# Woolllf_Open_Weeve.net
KiCad netlist of a schematic drawn in EAGLE
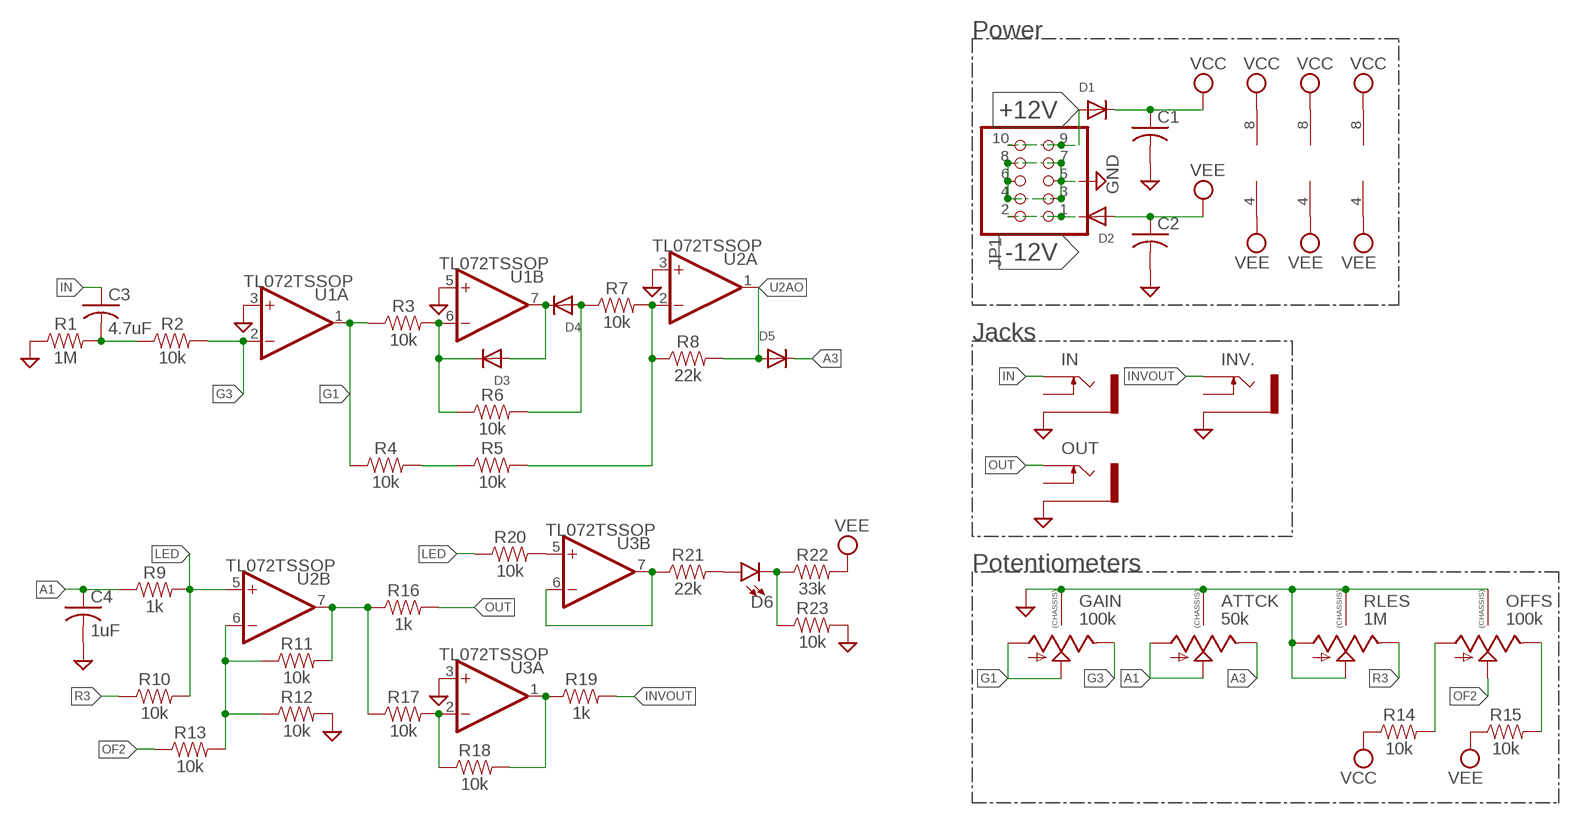
[diagram p0: schematic, sheet 1]

(export (version "E")
  (design (tool "Eeschema 10.0.6"))
  (components
    (comp (ref "ATTCK")
      (value "50k")
      (footprint "eagle-import:9MM_SNAP-IN_POT")
      (libsource (lib "eagle-import") (part "9MM_SNAP-IN_POT_CHASSIS"))
    )
    (comp (ref "C1")
      (value "C-USC1206")
      (footprint "eagle-import:C1206")
      (libsource (lib "eagle-import") (part "C-USC1206"))
    )
    (comp (ref "C2")
      (value "C-USC1206")
      (footprint "eagle-import:C1206")
      (libsource (lib "eagle-import") (part "C-USC1206"))
    )
    (comp (ref "C3")
      (value "4.7uF")
      (footprint "eagle-import:C0603")
      (libsource (lib "eagle-import") (part "C-USC0603"))
    )
    (comp (ref "C4")
      (value "1uF")
      (footprint "eagle-import:C0603")
      (libsource (lib "eagle-import") (part "C-USC0603"))
    )
    (comp (ref "D1")
      (value "DIODESOD-123")
      (footprint "eagle-import:SOD-123")
      (libsource (lib "eagle-import") (part "DIODESOD-123"))
    )
    (comp (ref "D2")
      (value "DIODESOD-123")
      (footprint "eagle-import:SOD-123")
      (libsource (lib "eagle-import") (part "DIODESOD-123"))
    )
    (comp (ref "D3")
      (value "DIODESOD-123")
      (footprint "eagle-import:SOD-123")
      (libsource (lib "eagle-import") (part "DIODESOD-123"))
    )
    (comp (ref "D4")
      (value "DIODESOD-123")
      (footprint "eagle-import:SOD-123")
      (libsource (lib "eagle-import") (part "DIODESOD-123"))
    )
    (comp (ref "D5")
      (value "DIODESOD-123")
      (footprint "eagle-import:SOD-123")
      (libsource (lib "eagle-import") (part "DIODESOD-123"))
    )
    (comp (ref "D6")
      (value "LED3MM")
      (footprint "eagle-import:LED_3MM")
      (libsource (lib "eagle-import") (part "LED3MM"))
    )
    (comp (ref "GAIN")
      (value "100k")
      (footprint "eagle-import:9MM_SNAP-IN_POT")
      (libsource (lib "eagle-import") (part "9MM_SNAP-IN_POT_CHASSIS"))
    )
    (comp (ref "IN")
      (value "THONKICONNOLD")
      (footprint "eagle-import:THONKICONN")
      (libsource (lib "eagle-import") (part "THONKICONNOLD"))
    )
    (comp (ref "INV.")
      (value "THONKICONNOLD")
      (footprint "eagle-import:THONKICONN")
      (libsource (lib "eagle-import") (part "THONKICONNOLD"))
    )
    (comp (ref "JP1")
      (value "PINHD-2X5")
      (footprint "eagle-import:2X05")
      (libsource (lib "eagle-import") (part "PINHD-2X5"))
    )
    (comp (ref "OFFS")
      (value "100k")
      (footprint "eagle-import:9MM_SNAP-IN_POT")
      (libsource (lib "eagle-import") (part "9MM_SNAP-IN_POT_CHASSIS"))
    )
    (comp (ref "OUT")
      (value "THONKICONNOLD")
      (footprint "eagle-import:THONKICONN")
      (libsource (lib "eagle-import") (part "THONKICONNOLD"))
    )
    (comp (ref "R1")
      (value "1M")
      (footprint "eagle-import:0603")
      (libsource (lib "eagle-import") (part "RESISTOR0603"))
    )
    (comp (ref "R2")
      (value "10k")
      (footprint "eagle-import:0603")
      (libsource (lib "eagle-import") (part "RESISTOR0603"))
    )
    (comp (ref "R3")
      (value "10k")
      (footprint "eagle-import:0603")
      (libsource (lib "eagle-import") (part "RESISTOR0603"))
    )
    (comp (ref "R4")
      (value "10k")
      (footprint "eagle-import:0603")
      (libsource (lib "eagle-import") (part "RESISTOR0603"))
    )
    (comp (ref "R5")
      (value "10k")
      (footprint "eagle-import:0603")
      (libsource (lib "eagle-import") (part "RESISTOR0603"))
    )
    (comp (ref "R6")
      (value "10k")
      (footprint "eagle-import:0603")
      (libsource (lib "eagle-import") (part "RESISTOR0603"))
    )
    (comp (ref "R7")
      (value "10k")
      (footprint "eagle-import:0603")
      (libsource (lib "eagle-import") (part "RESISTOR0603"))
    )
    (comp (ref "R8")
      (value "22k")
      (footprint "eagle-import:0603")
      (libsource (lib "eagle-import") (part "RESISTOR0603"))
    )
    (comp (ref "R9")
      (value "1k")
      (footprint "eagle-import:0603")
      (libsource (lib "eagle-import") (part "RESISTOR0603"))
    )
    (comp (ref "R10")
      (value "10k")
      (footprint "eagle-import:0603")
      (libsource (lib "eagle-import") (part "RESISTOR0603"))
    )
    (comp (ref "R11")
      (value "10k")
      (footprint "eagle-import:0603")
      (libsource (lib "eagle-import") (part "RESISTOR0603"))
    )
    (comp (ref "R12")
      (value "10k")
      (footprint "eagle-import:0603")
      (libsource (lib "eagle-import") (part "RESISTOR0603"))
    )
    (comp (ref "R13")
      (value "10k")
      (footprint "eagle-import:0603")
      (libsource (lib "eagle-import") (part "RESISTOR0603"))
    )
    (comp (ref "R14")
      (value "10k")
      (footprint "eagle-import:0603")
      (libsource (lib "eagle-import") (part "RESISTOR0603"))
    )
    (comp (ref "R15")
      (value "10k")
      (footprint "eagle-import:0603")
      (libsource (lib "eagle-import") (part "RESISTOR0603"))
    )
    (comp (ref "R16")
      (value "1k")
      (footprint "eagle-import:0603")
      (libsource (lib "eagle-import") (part "RESISTOR0603"))
    )
    (comp (ref "R17")
      (value "10k")
      (footprint "eagle-import:0603")
      (libsource (lib "eagle-import") (part "RESISTOR0603"))
    )
    (comp (ref "R18")
      (value "10k")
      (footprint "eagle-import:0603")
      (libsource (lib "eagle-import") (part "RESISTOR0603"))
    )
    (comp (ref "R19")
      (value "1k")
      (footprint "eagle-import:0603")
      (libsource (lib "eagle-import") (part "RESISTOR0603"))
    )
    (comp (ref "R20")
      (value "10k")
      (footprint "eagle-import:0603")
      (libsource (lib "eagle-import") (part "RESISTOR0603"))
    )
    (comp (ref "R21")
      (value "22k")
      (footprint "eagle-import:0603")
      (libsource (lib "eagle-import") (part "RESISTOR0603"))
    )
    (comp (ref "R22")
      (value "33k")
      (footprint "eagle-import:0603")
      (libsource (lib "eagle-import") (part "RESISTOR0603"))
    )
    (comp (ref "R23")
      (value "10k")
      (footprint "eagle-import:0603")
      (libsource (lib "eagle-import") (part "RESISTOR0603"))
    )
    (comp (ref "RLES")
      (value "1M")
      (footprint "eagle-import:9MM_SNAP-IN_POT")
      (libsource (lib "eagle-import") (part "9MM_SNAP-IN_POT_CHASSIS"))
    )
    (comp (ref "U1")
      (value "TL072TSSOP")
      (footprint "eagle-import:TSSOP-8")
      (libsource (lib "eagle-import") (part "TL072TSSOP"))
    )
    (comp (ref "U2")
      (value "TL072TSSOP")
      (footprint "eagle-import:TSSOP-8")
      (libsource (lib "eagle-import") (part "TL072TSSOP"))
    )
    (comp (ref "U3")
      (value "TL072TSSOP")
      (footprint "eagle-import:TSSOP-8")
      (libsource (lib "eagle-import") (part "TL072TSSOP"))
    )
  )
  (nets
    (net (code "1") (name "+12V") (class "Default")
      (node (ref "D1") (pin "A") (pinfunction "A_A") (pintype "passive"))
      (node (ref "JP1") (pin "10") (pinfunction "10_10") (pintype "passive"))
      (node (ref "JP1") (pin "9") (pinfunction "9_9") (pintype "passive"))
    )
    (net (code "2") (name "-12V") (class "Default")
      (node (ref "D2") (pin "C") (pinfunction "C_C") (pintype "passive"))
      (node (ref "JP1") (pin "1") (pinfunction "1_1") (pintype "passive"))
      (node (ref "JP1") (pin "2") (pinfunction "2_2") (pintype "passive"))
    )
    (net (code "3") (name "A1") (class "Default")
      (node (ref "ATTCK") (pin "1") (pinfunction "A_1") (pintype "passive"))
      (node (ref "ATTCK") (pin "2") (pinfunction "S_2") (pintype "passive"))
      (node (ref "C4") (pin "1") (pinfunction "1_1") (pintype "passive"))
      (node (ref "R9") (pin "1") (pinfunction "1_1") (pintype "passive"))
    )
    (net (code "4") (name "A3") (class "Default")
      (node (ref "ATTCK") (pin "3") (pinfunction "E_3") (pintype "passive"))
      (node (ref "D5") (pin "C") (pinfunction "C_C") (pintype "passive"))
    )
    (net (code "5") (name "G1") (class "Default")
      (node (ref "GAIN") (pin "1") (pinfunction "A_1") (pintype "passive"))
      (node (ref "GAIN") (pin "2") (pinfunction "S_2") (pintype "passive"))
      (node (ref "R3") (pin "1") (pinfunction "1_1") (pintype "passive"))
      (node (ref "R4") (pin "1") (pinfunction "1_1") (pintype "passive"))
      (node (ref "U1") (pin "1") (pinfunction "OUT_1") (pintype "output"))
    )
    (net (code "6") (name "G3") (class "Default")
      (node (ref "GAIN") (pin "3") (pinfunction "E_3") (pintype "passive"))
      (node (ref "R2") (pin "2") (pinfunction "2_2") (pintype "passive"))
      (node (ref "U1") (pin "2") (pinfunction "-IN_2") (pintype "input"))
    )
    (net (code "7") (name "GND") (class "Default")
      (node (ref "ATTCK") (pin "CHASSIS1") (pinfunction "P$1_CHASSIS1") (pintype "passive"))
      (node (ref "ATTCK") (pin "CHASSIS2") (pinfunction "P$1_CHASSIS2") (pintype "passive"))
      (node (ref "C1") (pin "2") (pinfunction "2_2") (pintype "passive"))
      (node (ref "C2") (pin "2") (pinfunction "2_2") (pintype "passive"))
      (node (ref "C4") (pin "2") (pinfunction "2_2") (pintype "passive"))
      (node (ref "GAIN") (pin "CHASSIS1") (pinfunction "P$1_CHASSIS1") (pintype "passive"))
      (node (ref "GAIN") (pin "CHASSIS2") (pinfunction "P$1_CHASSIS2") (pintype "passive"))
      (node (ref "IN") (pin "P$1_SLEEVE") (pinfunction "SLEEVE_P$1_SLEEVE") (pintype "passive"))
      (node (ref "INV.") (pin "P$1_SLEEVE") (pinfunction "SLEEVE_P$1_SLEEVE") (pintype "passive"))
      (node (ref "JP1") (pin "3") (pinfunction "3_3") (pintype "passive"))
      (node (ref "JP1") (pin "4") (pinfunction "4_4") (pintype "passive"))
      (node (ref "JP1") (pin "5") (pinfunction "5_5") (pintype "passive"))
      (node (ref "JP1") (pin "6") (pinfunction "6_6") (pintype "passive"))
      (node (ref "JP1") (pin "7") (pinfunction "7_7") (pintype "passive"))
      (node (ref "JP1") (pin "8") (pinfunction "8_8") (pintype "passive"))
      (node (ref "OFFS") (pin "CHASSIS1") (pinfunction "P$1_CHASSIS1") (pintype "passive"))
      (node (ref "OFFS") (pin "CHASSIS2") (pinfunction "P$1_CHASSIS2") (pintype "passive"))
      (node (ref "OUT") (pin "P$1_SLEEVE") (pinfunction "SLEEVE_P$1_SLEEVE") (pintype "passive"))
      (node (ref "R1") (pin "1") (pinfunction "1_1") (pintype "passive"))
      (node (ref "R12") (pin "2") (pinfunction "2_2") (pintype "passive"))
      (node (ref "R23") (pin "2") (pinfunction "2_2") (pintype "passive"))
      (node (ref "RLES") (pin "1") (pinfunction "A_1") (pintype "passive"))
      (node (ref "RLES") (pin "2") (pinfunction "S_2") (pintype "passive"))
      (node (ref "RLES") (pin "CHASSIS1") (pinfunction "P$1_CHASSIS1") (pintype "passive"))
      (node (ref "RLES") (pin "CHASSIS2") (pinfunction "P$1_CHASSIS2") (pintype "passive"))
      (node (ref "U1") (pin "3") (pinfunction "+IN_3") (pintype "input"))
      (node (ref "U1") (pin "5") (pinfunction "+IN_5") (pintype "input"))
      (node (ref "U2") (pin "3") (pinfunction "+IN_3") (pintype "input"))
      (node (ref "U3") (pin "3") (pinfunction "+IN_3") (pintype "input"))
    )
    (net (code "8") (name "IN") (class "Default")
      (node (ref "C3") (pin "1") (pinfunction "1_1") (pintype "passive"))
      (node (ref "IN") (pin "P$3_TIP") (pinfunction "TIP_P$3_TIP") (pintype "passive"))
    )
    (net (code "9") (name "INVOUT") (class "Default")
      (node (ref "INV.") (pin "P$3_TIP") (pinfunction "TIP_P$3_TIP") (pintype "passive"))
      (node (ref "R19") (pin "2") (pinfunction "2_2") (pintype "passive"))
    )
    (net (code "10") (name "LED") (class "Default")
      (node (ref "R10") (pin "2") (pinfunction "2_2") (pintype "passive"))
      (node (ref "R20") (pin "1") (pinfunction "1_1") (pintype "passive"))
      (node (ref "R9") (pin "2") (pinfunction "2_2") (pintype "passive"))
      (node (ref "U2") (pin "5") (pinfunction "+IN_5") (pintype "input"))
    )
    (net (code "11") (name "Net-(C3-Pad2)") (class "Default")
      (node (ref "C3") (pin "2") (pinfunction "2_2") (pintype "passive"))
      (node (ref "R1") (pin "2") (pinfunction "2_2") (pintype "passive"))
      (node (ref "R2") (pin "1") (pinfunction "1_1") (pintype "passive"))
    )
    (net (code "12") (name "Net-(D4-PadA)") (class "Default")
      (node (ref "D4") (pin "A") (pinfunction "A_A") (pintype "passive"))
      (node (ref "R6") (pin "2") (pinfunction "2_2") (pintype "passive"))
      (node (ref "R7") (pin "1") (pinfunction "1_1") (pintype "passive"))
    )
    (net (code "13") (name "Net-(D6-C)") (class "Default")
      (node (ref "D6") (pin "K") (pinfunction "C_K") (pintype "passive"))
      (node (ref "R22") (pin "1") (pinfunction "1_1") (pintype "passive"))
      (node (ref "R23") (pin "1") (pinfunction "1_1") (pintype "passive"))
    )
    (net (code "14") (name "Net-(D6-PadA)") (class "Default")
      (node (ref "D6") (pin "A") (pinfunction "A_A") (pintype "passive"))
      (node (ref "R21") (pin "2") (pinfunction "2_2") (pintype "passive"))
    )
    (net (code "15") (name "Net-(OFFS-A)") (class "Default")
      (node (ref "OFFS") (pin "1") (pinfunction "A_1") (pintype "passive"))
      (node (ref "R14") (pin "2") (pinfunction "2_2") (pintype "passive"))
    )
    (net (code "16") (name "Net-(OFFS-E)") (class "Default")
      (node (ref "OFFS") (pin "3") (pinfunction "E_3") (pintype "passive"))
      (node (ref "R15") (pin "2") (pinfunction "2_2") (pintype "passive"))
    )
    (net (code "17") (name "Net-(R4-Pad2)") (class "Default")
      (node (ref "R4") (pin "2") (pinfunction "2_2") (pintype "passive"))
      (node (ref "R5") (pin "1") (pinfunction "1_1") (pintype "passive"))
    )
    (net (code "18") (name "Net-(U1B--IN)") (class "Default")
      (node (ref "D3") (pin "C") (pinfunction "C_C") (pintype "passive"))
      (node (ref "R3") (pin "2") (pinfunction "2_2") (pintype "passive"))
      (node (ref "R6") (pin "1") (pinfunction "1_1") (pintype "passive"))
      (node (ref "U1") (pin "6") (pinfunction "-IN_6") (pintype "input"))
    )
    (net (code "19") (name "Net-(U1B-OUT)") (class "Default")
      (node (ref "D3") (pin "A") (pinfunction "A_A") (pintype "passive"))
      (node (ref "D4") (pin "C") (pinfunction "C_C") (pintype "passive"))
      (node (ref "U1") (pin "7") (pinfunction "OUT_7") (pintype "output"))
    )
    (net (code "20") (name "Net-(U2A--IN)") (class "Default")
      (node (ref "R5") (pin "2") (pinfunction "2_2") (pintype "passive"))
      (node (ref "R7") (pin "2") (pinfunction "2_2") (pintype "passive"))
      (node (ref "R8") (pin "1") (pinfunction "1_1") (pintype "passive"))
      (node (ref "U2") (pin "2") (pinfunction "-IN_2") (pintype "input"))
    )
    (net (code "21") (name "Net-(U2B--IN)") (class "Default")
      (node (ref "R11") (pin "1") (pinfunction "1_1") (pintype "passive"))
      (node (ref "R12") (pin "1") (pinfunction "1_1") (pintype "passive"))
      (node (ref "R13") (pin "2") (pinfunction "2_2") (pintype "passive"))
      (node (ref "U2") (pin "6") (pinfunction "-IN_6") (pintype "input"))
    )
    (net (code "22") (name "Net-(U2B-OUT)") (class "Default")
      (node (ref "R11") (pin "2") (pinfunction "2_2") (pintype "passive"))
      (node (ref "R16") (pin "1") (pinfunction "1_1") (pintype "passive"))
      (node (ref "R17") (pin "1") (pinfunction "1_1") (pintype "passive"))
      (node (ref "U2") (pin "7") (pinfunction "OUT_7") (pintype "output"))
    )
    (net (code "23") (name "Net-(U3A--IN)") (class "Default")
      (node (ref "R17") (pin "2") (pinfunction "2_2") (pintype "passive"))
      (node (ref "R18") (pin "1") (pinfunction "1_1") (pintype "passive"))
      (node (ref "U3") (pin "2") (pinfunction "-IN_2") (pintype "input"))
    )
    (net (code "24") (name "Net-(U3A-OUT)") (class "Default")
      (node (ref "R18") (pin "2") (pinfunction "2_2") (pintype "passive"))
      (node (ref "R19") (pin "1") (pinfunction "1_1") (pintype "passive"))
      (node (ref "U3") (pin "1") (pinfunction "OUT_1") (pintype "output"))
    )
    (net (code "25") (name "Net-(U3B-+IN)") (class "Default")
      (node (ref "R20") (pin "2") (pinfunction "2_2") (pintype "passive"))
      (node (ref "U3") (pin "5") (pinfunction "+IN_5") (pintype "input"))
    )
    (net (code "26") (name "Net-(U3B--IN)") (class "Default")
      (node (ref "R21") (pin "1") (pinfunction "1_1") (pintype "passive"))
      (node (ref "U3") (pin "6") (pinfunction "-IN_6") (pintype "input"))
      (node (ref "U3") (pin "7") (pinfunction "OUT_7") (pintype "output"))
    )
    (net (code "27") (name "OF2") (class "Default")
      (node (ref "OFFS") (pin "2") (pinfunction "S_2") (pintype "passive"))
      (node (ref "R13") (pin "1") (pinfunction "1_1") (pintype "passive"))
    )
    (net (code "28") (name "OUT") (class "Default")
      (node (ref "OUT") (pin "P$3_TIP") (pinfunction "TIP_P$3_TIP") (pintype "passive"))
      (node (ref "R16") (pin "2") (pinfunction "2_2") (pintype "passive"))
    )
    (net (code "29") (name "R3") (class "Default")
      (node (ref "R10") (pin "1") (pinfunction "1_1") (pintype "passive"))
      (node (ref "RLES") (pin "3") (pinfunction "E_3") (pintype "passive"))
    )
    (net (code "30") (name "U2AO") (class "Default")
      (node (ref "D5") (pin "A") (pinfunction "A_A") (pintype "passive"))
      (node (ref "R8") (pin "2") (pinfunction "2_2") (pintype "passive"))
      (node (ref "U2") (pin "1") (pinfunction "OUT_1") (pintype "output"))
    )
    (net (code "31") (name "VCC") (class "Default")
      (node (ref "C1") (pin "1") (pinfunction "1_1") (pintype "passive"))
      (node (ref "D1") (pin "C") (pinfunction "C_C") (pintype "passive"))
      (node (ref "R14") (pin "1") (pinfunction "1_1") (pintype "passive"))
      (node (ref "U1") (pin "8") (pinfunction "V+_8") (pintype "power_in"))
      (node (ref "U2") (pin "8") (pinfunction "V+_8") (pintype "power_in"))
      (node (ref "U3") (pin "8") (pinfunction "V+_8") (pintype "power_in"))
    )
    (net (code "32") (name "VEE") (class "Default")
      (node (ref "C2") (pin "1") (pinfunction "1_1") (pintype "passive"))
      (node (ref "D2") (pin "A") (pinfunction "A_A") (pintype "passive"))
      (node (ref "R15") (pin "1") (pinfunction "1_1") (pintype "passive"))
      (node (ref "R22") (pin "2") (pinfunction "2_2") (pintype "passive"))
      (node (ref "U1") (pin "4") (pinfunction "V-_4") (pintype "power_in"))
      (node (ref "U2") (pin "4") (pinfunction "V-_4") (pintype "power_in"))
      (node (ref "U3") (pin "4") (pinfunction "V-_4") (pintype "power_in"))
    )
    (net (code "33") (name "unconnected-(IN-SWITCH-PadP$2_SWITCH)") (class "Default")
      (node (ref "IN") (pin "P$2_SWITCH") (pinfunction "SWITCH_P$2_SWITCH") (pintype "passive"))
    )
    (net (code "34") (name "unconnected-(INV.-SWITCH-PadP$2_SWITCH)") (class "Default")
      (node (ref "INV.") (pin "P$2_SWITCH") (pinfunction "SWITCH_P$2_SWITCH") (pintype "passive"))
    )
    (net (code "35") (name "unconnected-(OUT-SWITCH-PadP$2_SWITCH)") (class "Default")
      (node (ref "OUT") (pin "P$2_SWITCH") (pinfunction "SWITCH_P$2_SWITCH") (pintype "passive"))
    )
  )
)
